# RF.net
KiCad netlist of a schematic drawn in Altium Designer
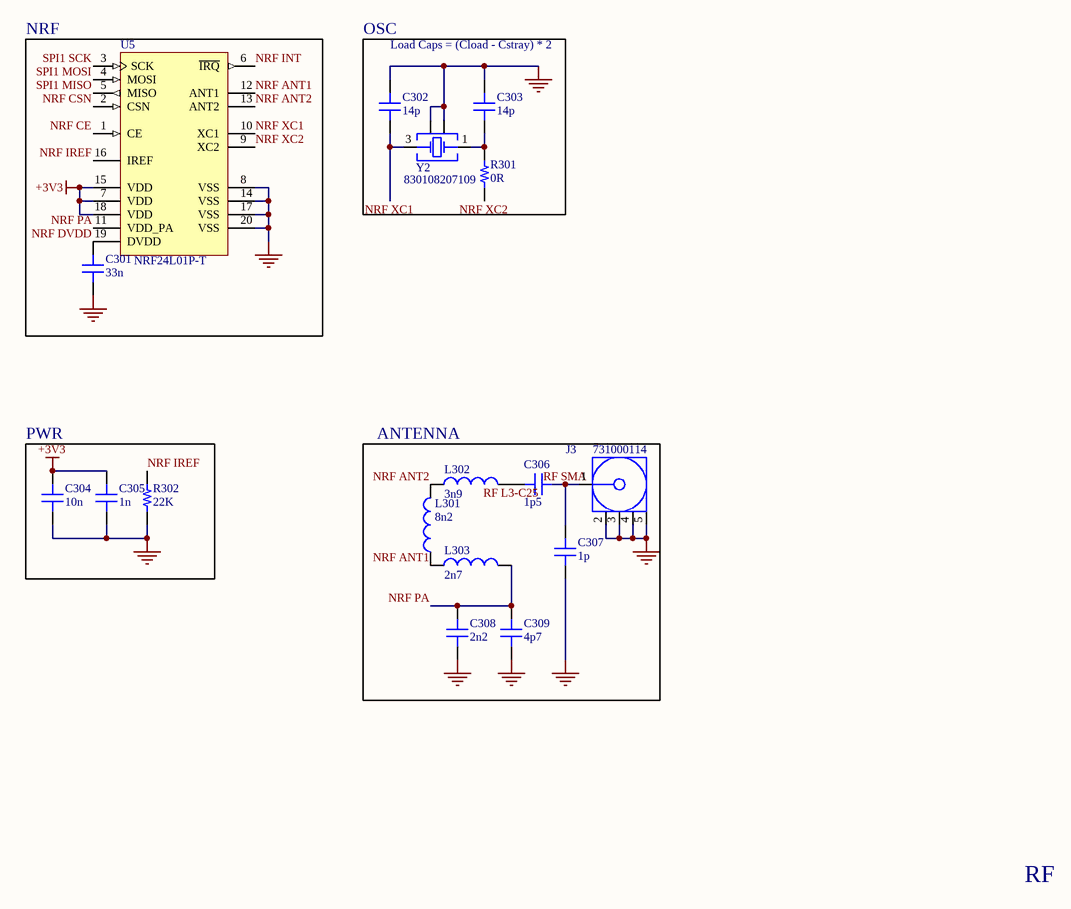
[diagram p0: RF.SchDoc]

(export (version "E")
  (design (tool "Eeschema 10.0.6"))
  (components
    (comp (ref "C301")
      (value "33n")
      (footprint "CAP 0402_1005")
      (description "CAP CER 33PF 16V X7R 0402")
      (fields (field (name "PART NUMBER") "C0402C330J4RACAUTO") (field (name "MANUFACTURER") "KEMET"))
      (libsource (lib "Celestial Altium Library - altium_library") (part "Capacitor"))
    )
    (comp (ref "C302")
      (value "14p")
      (footprint "CAP 0402_1005")
      (description "CAP CER 14PF 50V C0G/NP0 0402")
      (fields (field (name "PART NUMBER") "GJM1555C1H140GB01D"))
      (libsource (lib "Celestial Altium Library - altium_library") (part "Capacitor"))
    )
    (comp (ref "C303")
      (value "14p")
      (footprint "CAP 0402_1005")
      (description "CAP CER 14PF 50V C0G/NP0 0402")
      (fields (field (name "PART NUMBER") "GJM1555C1H140GB01D"))
      (libsource (lib "Celestial Altium Library - altium_library") (part "Capacitor"))
    )
    (comp (ref "C304")
      (value "10n")
      (footprint "CAP 0402_1005")
      (description "CAP CER 0402 10NF 16V X7R 10%")
      (fields (field (name "PART NUMBER") "C0402C103K4REC7867") (field (name "MANUFACTURER") "KEMET"))
      (libsource (lib "Celestial Altium Library - altium_library") (part "Capacitor"))
    )
    (comp (ref "C305")
      (value "1n")
      (footprint "CAP 0402_1005")
      (description "CAP CER 0402 10NF 16V X7R 10%")
      (fields (field (name "PART NUMBER") "C0402C103K4REC7867") (field (name "MANUFACTURER") "KEMET"))
      (libsource (lib "Celestial Altium Library - altium_library") (part "Capacitor"))
    )
    (comp (ref "C306")
      (value "1p5")
      (footprint "CAP 0402_1005")
      (description "CAP CER 0402 10NF 16V X7R 10%")
      (fields (field (name "PART NUMBER") "C0402C103K4REC7867") (field (name "MANUFACTURER") "KEMET"))
      (libsource (lib "Celestial Altium Library - altium_library") (part "Capacitor"))
    )
    (comp (ref "C307")
      (value "1p")
      (footprint "CAP 0402_1005")
      (description "CAP CER 0402 10NF 16V X7R 10%")
      (fields (field (name "PART NUMBER") "C0402C103K4REC7867") (field (name "MANUFACTURER") "KEMET"))
      (libsource (lib "Celestial Altium Library - altium_library") (part "Capacitor"))
    )
    (comp (ref "C308")
      (value "2n2")
      (footprint "CAP 0402_1005")
      (description "CAP CER 0402 10NF 16V X7R 10%")
      (fields (field (name "PART NUMBER") "C0402C103K4REC7867") (field (name "MANUFACTURER") "KEMET"))
      (libsource (lib "Celestial Altium Library - altium_library") (part "Capacitor"))
    )
    (comp (ref "C309")
      (value "4p7")
      (footprint "CAP 0402_1005")
      (description "CAP CER 0402 10NF 16V X7R 10%")
      (fields (field (name "PART NUMBER") "C0402C103K4REC7867") (field (name "MANUFACTURER") "KEMET"))
      (libsource (lib "Celestial Altium Library - altium_library") (part "Capacitor"))
    )
    (comp (ref "J3")
      (value "731000114")
      (footprint "MOLX-731000114_V")
      (description "SMA Right-Angle PCB Jack Receptacle, Brass Body, Gold Plated, 50 Ohm, 5-Pin THD, RoHS, Tray")
      (fields (field (name "MANUFACTURER") "Molex"))
      (libsource (lib "Altium Content Vault") (part "CN-S-4F-RF5"))
    )
    (comp (ref "L301")
      (value "8n2")
      (footprint "WE-TCI_0402")
      (description "744901039 Fixed Ind 3.9NH 340MA 500MOHM Sm")
      (libsource (lib "Altium Content Vault") (part "Inductor - 1"))
    )
    (comp (ref "L302")
      (value "3n9")
      (footprint "WE-TCI_0402")
      (description "744901039 Fixed Ind 3.9NH 340MA 500MOHM Sm")
      (libsource (lib "Altium Content Vault") (part "Inductor - 1"))
    )
    (comp (ref "L303")
      (value "2n7")
      (footprint "WE-TCI_0402")
      (description "744901039 Fixed Ind 3.9NH 340MA 500MOHM Sm")
      (libsource (lib "Altium Content Vault") (part "Inductor - 1"))
    )
    (comp (ref "R301")
      (value "0R")
      (footprint "RES 0402_1005")
      (description "0402 JUMPER ON TAPE AND REEL")
      (fields (field (name "PART NUMBER") "5112"))
      (libsource (lib "Celestial Altium Library - altium_library") (part "Resistor"))
    )
    (comp (ref "R302")
      (value "22K")
      (footprint "RES 0402_1005")
      (description "RES 22.1K OHM 1% 1/16W 0402")
      (fields (field (name "PART NUMBER") "RC0402FR-0722K1L") (field (name "MANUFACTURER") "Yageo"))
      (libsource (lib "Celestial Altium Library - altium_library") (part "Resistor"))
    )
    (comp (ref "U5")
      (value "NRF24L01P-T")
      (footprint "NRSC-QFN-20_L")
      (description "Single Chip Transceiver, 2.4 GHz, 60 mW, 1.9 to 3.6 V, -40 to 85 degC, 20-Pin QFN, RoHS, Tray")
      (fields (field (name "MANUFACTURER") "Nordic Semiconductor"))
      (libsource (lib "Altium Content Vault") (part "NRSC-NRF24L01P-QFN-20"))
    )
    (comp (ref "Y2")
      (value "830108207109")
      (footprint "WE-XTAL_CFPX-180")
      (description "830108207109 WE-XTAL Quartz Crystal")
      (libsource (lib "Altium Content Vault") (part "WE-XTAL_CFPX-180"))
    )
  )
  (nets
    (net (code "1") (name "+3V3") (class "Default")
      (node (ref "C304") (pin "2") (pinfunction "2_2") (pintype "passive"))
      (node (ref "C305") (pin "2") (pinfunction "2_2") (pintype "passive"))
      (node (ref "U5") (pin "15") (pinfunction "VDD_15") (pintype "power_in"))
      (node (ref "U5") (pin "18") (pinfunction "VDD_18") (pintype "power_in"))
      (node (ref "U5") (pin "7") (pinfunction "VDD_7") (pintype "power_in"))
    )
    (net (code "2") (name "/NRF ANT1") (class "Default")
      (node (ref "L301") (pin "1") (pinfunction "1_1") (pintype "passive"))
      (node (ref "L303") (pin "1") (pinfunction "1_1") (pintype "passive"))
      (node (ref "U5") (pin "12") (pinfunction "ANT1_12") (pintype "passive"))
    )
    (net (code "3") (name "/NRF ANT2") (class "Default")
      (node (ref "L301") (pin "2") (pinfunction "2_2") (pintype "passive"))
      (node (ref "L302") (pin "1") (pinfunction "1_1") (pintype "passive"))
      (node (ref "U5") (pin "13") (pinfunction "ANT2_13") (pintype "passive"))
    )
    (net (code "4") (name "/NRF CE") (class "Default")
      (node (ref "U5") (pin "1") (pinfunction "CE_1") (pintype "input"))
    )
    (net (code "5") (name "/NRF CSN") (class "Default")
      (node (ref "U5") (pin "2") (pinfunction "CSN_2") (pintype "input"))
    )
    (net (code "6") (name "/NRF DVDD") (class "Default")
      (node (ref "C301") (pin "2") (pinfunction "2_2") (pintype "passive"))
      (node (ref "U5") (pin "19") (pinfunction "DVDD_19") (pintype "power_in"))
    )
    (net (code "7") (name "/NRF INT") (class "Default")
      (node (ref "U5") (pin "6") (pinfunction "~{IRQ}_6") (pintype "output"))
    )
    (net (code "8") (name "/NRF IREF") (class "Default")
      (node (ref "R302") (pin "1") (pinfunction "1_1") (pintype "passive"))
      (node (ref "U5") (pin "16") (pinfunction "IREF_16") (pintype "passive"))
    )
    (net (code "9") (name "/NRF PA") (class "Default")
      (node (ref "C308") (pin "2") (pinfunction "2_2") (pintype "passive"))
      (node (ref "C309") (pin "2") (pinfunction "2_2") (pintype "passive"))
      (node (ref "L303") (pin "2") (pinfunction "2_2") (pintype "passive"))
      (node (ref "U5") (pin "11") (pinfunction "VDD_PA_11") (pintype "power_in"))
    )
    (net (code "10") (name "/NRF XC1") (class "Default")
      (node (ref "C302") (pin "1") (pinfunction "1_1") (pintype "passive"))
      (node (ref "U5") (pin "10") (pinfunction "XC1_10") (pintype "passive"))
      (node (ref "Y2") (pin "3") (pinfunction "Crystal_3") (pintype "passive"))
    )
    (net (code "11") (name "/NRF XC2") (class "Default")
      (node (ref "R301") (pin "2") (pinfunction "2_2") (pintype "passive"))
      (node (ref "U5") (pin "9") (pinfunction "XC2_9") (pintype "passive"))
    )
    (net (code "12") (name "/RF L3-C25") (class "Default")
      (node (ref "C306") (pin "2") (pinfunction "2_2") (pintype "passive"))
      (node (ref "L302") (pin "2") (pinfunction "2_2") (pintype "passive"))
    )
    (net (code "13") (name "/RF SMA") (class "Default")
      (node (ref "C306") (pin "1") (pinfunction "1_1") (pintype "passive"))
      (node (ref "C307") (pin "2") (pinfunction "2_2") (pintype "passive"))
      (node (ref "J3") (pin "1") (pinfunction "1_1") (pintype "passive"))
    )
    (net (code "14") (name "/SPI1 MISO") (class "Default")
      (node (ref "U5") (pin "5") (pinfunction "MISO_5") (pintype "output"))
    )
    (net (code "15") (name "/SPI1 MOSI") (class "Default")
      (node (ref "U5") (pin "4") (pinfunction "MOSI_4") (pintype "input"))
    )
    (net (code "16") (name "/SPI1 SCK") (class "Default")
      (node (ref "U5") (pin "3") (pinfunction "SCK_3") (pintype "input"))
    )
    (net (code "17") (name "GND") (class "Default")
      (node (ref "C301") (pin "1") (pinfunction "1_1") (pintype "passive"))
      (node (ref "C302") (pin "2") (pinfunction "2_2") (pintype "passive"))
      (node (ref "C303") (pin "2") (pinfunction "2_2") (pintype "passive"))
      (node (ref "C304") (pin "1") (pinfunction "1_1") (pintype "passive"))
      (node (ref "C305") (pin "1") (pinfunction "1_1") (pintype "passive"))
      (node (ref "C307") (pin "1") (pinfunction "1_1") (pintype "passive"))
      (node (ref "C308") (pin "1") (pinfunction "1_1") (pintype "passive"))
      (node (ref "C309") (pin "1") (pinfunction "1_1") (pintype "passive"))
      (node (ref "J3") (pin "2") (pinfunction "2_2") (pintype "passive"))
      (node (ref "J3") (pin "3") (pinfunction "3_3") (pintype "passive"))
      (node (ref "J3") (pin "4") (pinfunction "4_4") (pintype "passive"))
      (node (ref "J3") (pin "5") (pinfunction "5_5") (pintype "passive"))
      (node (ref "R302") (pin "2") (pinfunction "2_2") (pintype "passive"))
      (node (ref "U5") (pin "14") (pinfunction "VSS_14") (pintype "power_in"))
      (node (ref "U5") (pin "17") (pinfunction "VSS_17") (pintype "power_in"))
      (node (ref "U5") (pin "20") (pinfunction "VSS_20") (pintype "power_in"))
      (node (ref "U5") (pin "8") (pinfunction "VSS_8") (pintype "power_in"))
      (node (ref "Y2") (pin "2") (pinfunction "GND&Lid_2") (pintype "passive"))
      (node (ref "Y2") (pin "4") (pinfunction "GND&Lid_4") (pintype "passive"))
    )
    (net (code "18") (name "Net-(C303-Pad1)") (class "Default")
      (node (ref "C303") (pin "1") (pinfunction "1_1") (pintype "passive"))
      (node (ref "R301") (pin "1") (pinfunction "1_1") (pintype "passive"))
      (node (ref "Y2") (pin "1") (pinfunction "Crystal_1") (pintype "passive"))
    )
  )
)
